# Esquem_tico.net
KiCad netlist of a schematic drawn in Altium Designer
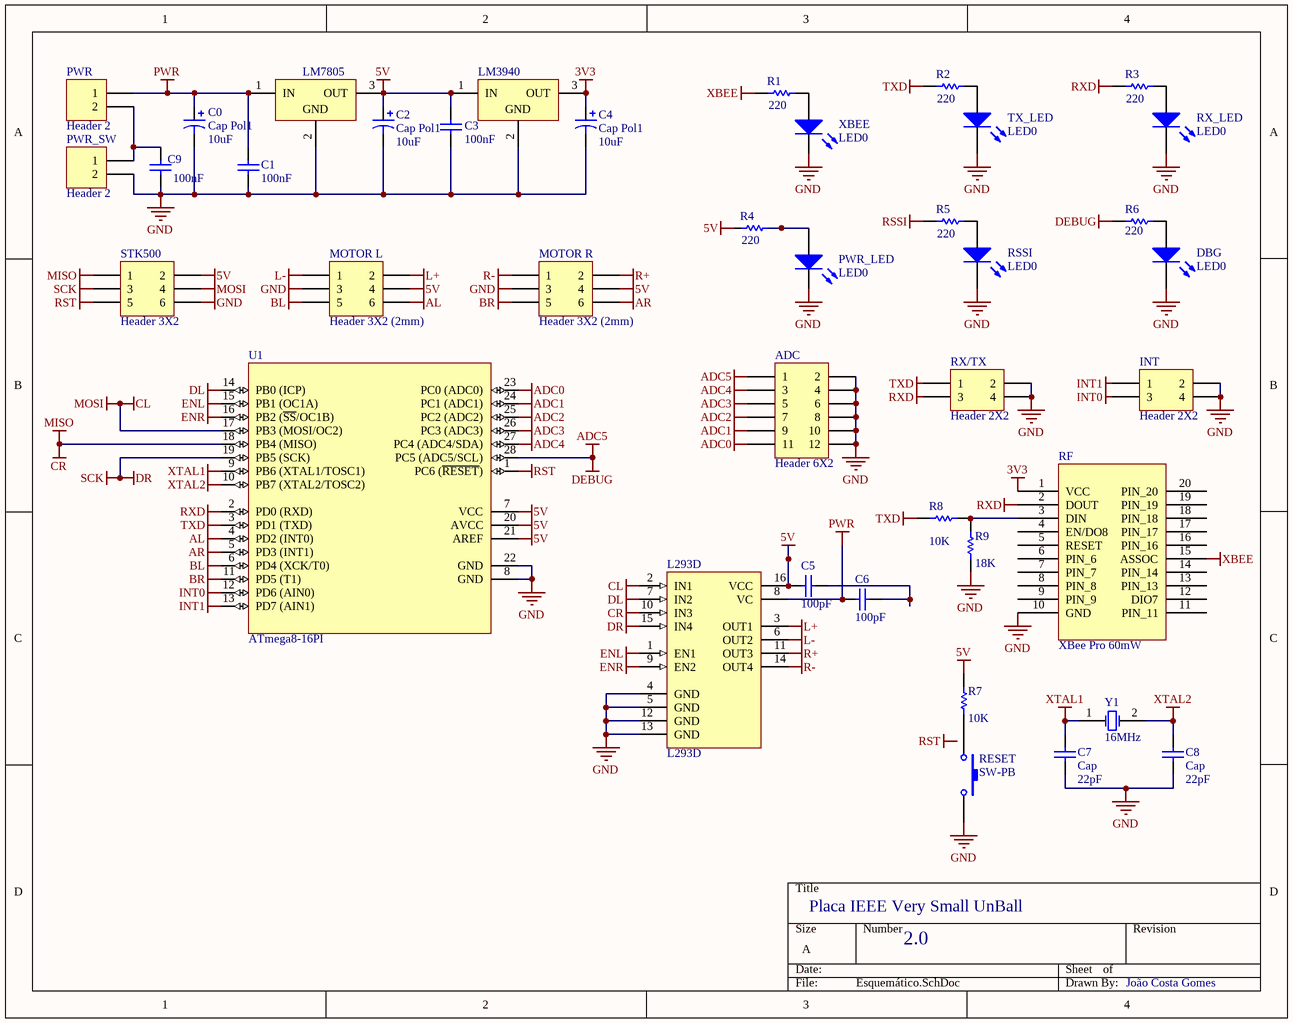
[diagram p0: Esquemático.SchDoc]

(export (version "E")
  (design (tool "Eeschema 10.0.6"))
  (components
    (comp (ref "ADC")
      (value "Header 6X2")
      (footprint "HDR2X6")
      (description "Header, 6-Pin, Dual row")
      (fields (field (name "PUBLISHER") "Altium Limited"))
      (libsource (lib "Miscellaneous Connectors") (part "Header 6X2"))
    )
    (comp (ref "C0")
      (value "Cap Pol1")
      (footprint "footprintsGPSrev1:B")
      (description "Polarized Capacitor (Radial)")
      (fields (field (name "ALTIUM_VALUE") "10uF") (field (name "PUBLISHER") "Altium Limited"))
      (libsource (lib "Miscellaneous Devices") (part "Cap Pol1"))
    )
    (comp (ref "C1")
      (value "100nF")
      (footprint "footprintsGPSrev1:C_NANO_HOLES")
      (description "Capacitor")
      (fields (field (name "Comment") "Cap") (field (name "PUBLISHER") "Altium Limited"))
      (libsource (lib "Miscellaneous Devices") (part "Cap"))
    )
    (comp (ref "C2")
      (value "Cap Pol1")
      (footprint "footprintsGPSrev1:B")
      (description "Polarized Capacitor (Radial)")
      (fields (field (name "ALTIUM_VALUE") "10uF") (field (name "PUBLISHER") "Altium Limited"))
      (libsource (lib "Miscellaneous Devices") (part "Cap Pol1"))
    )
    (comp (ref "C3")
      (value "100nF")
      (footprint "footprintsGPSrev1:C_NANO_HOLES")
      (description "Capacitor")
      (fields (field (name "Comment") "Cap") (field (name "PUBLISHER") "Altium Limited"))
      (libsource (lib "Miscellaneous Devices") (part "Cap"))
    )
    (comp (ref "C4")
      (value "Cap Pol1")
      (footprint "footprintsGPSrev1:B")
      (description "Polarized Capacitor (Radial)")
      (fields (field (name "ALTIUM_VALUE") "10uF") (field (name "PUBLISHER") "Altium Limited"))
      (libsource (lib "Miscellaneous Devices") (part "Cap Pol1"))
    )
    (comp (ref "C5")
      (value "100pF")
      (footprint "footprintsGPSrev1:C_NANO_HOLES")
      (description "Capacitor")
      (fields (field (name "Comment") "Cap") (field (name "PUBLISHER") "Altium Limited"))
      (libsource (lib "Miscellaneous Devices") (part "Cap"))
    )
    (comp (ref "C6")
      (value "100pF")
      (footprint "C_NANO_HOLES")
      (description "Capacitor")
      (fields (field (name "Comment") "Cap") (field (name "PUBLISHER") "Altium Limited"))
      (libsource (lib "Miscellaneous Devices") (part "Cap"))
    )
    (comp (ref "C7")
      (value "Cap")
      (footprint "C_NANO_HOLES")
      (description "Capacitor")
      (fields (field (name "ALTIUM_VALUE") "22pF") (field (name "PUBLISHER") "Altium Limited"))
      (libsource (lib "Miscellaneous Devices") (part "Cap"))
    )
    (comp (ref "C8")
      (value "Cap")
      (footprint "C_NANO_HOLES")
      (description "Capacitor")
      (fields (field (name "ALTIUM_VALUE") "22pF") (field (name "PUBLISHER") "Altium Limited"))
      (libsource (lib "Miscellaneous Devices") (part "Cap"))
    )
    (comp (ref "C9")
      (value "100nF")
      (footprint "footprintsGPSrev1:C_NANO_HOLES")
      (description "Capacitor")
      (fields (field (name "Comment") "Cap") (field (name "PUBLISHER") "Altium Limited"))
      (libsource (lib "Miscellaneous Devices") (part "Cap"))
    )
    (comp (ref "DBG")
      (value "LED0")
      (footprint "B")
      (description "Typical INFRARED GaAs LED")
      (fields (field (name "PUBLISHER") "Altium Limited"))
      (libsource (lib "Miscellaneous Devices") (part "LED0"))
    )
    (comp (ref "INT")
      (value "Header 2X2")
      (footprint "HDR2X2")
      (description "Header, 2-Pin, Dual row")
      (fields (field (name "PUBLISHER") "Altium Limited"))
      (libsource (lib "Miscellaneous Connectors") (part "Header 2X2"))
    )
    (comp (ref "L293D")
      (value "L293D")
      (footprint "DIP16")
      (description "Push-Pull Four Channel Driver With Diode")
      (fields (field (name "PUBLISHER") "Altium Limited"))
      (libsource (lib "ST Interface DC & Stepper Motor Controller") (part "L293D"))
    )
    (comp (ref "LM3940")
      (value "LM3940IT-3.3")
      (footprint "T03B")
      (description "1A Low Dropout Regulator for 5V to 3.3V Conversion")
      (fields
        (field (name "MANUFACTURER") "National Semiconductor")
        (field (name "DIGIKEYPARTNUMBER") "LM3940IT-3.3-ND")
        (field (name "PUBLISHER") "Altium Limited")
      )
      (libsource (lib "NSC LDO") (part "LM3940IT-3.3"))
    )
    (comp (ref "LM7805")
      (value "µA7805CKC")
      (footprint "KC03")
      (description "Positive-Voltage Regulator")
      (fields (field (name "PUBLISHER") "Altium Limited"))
      (libsource (lib "TI Power Mgt Voltage Regulator") (part "µA7805CKC"))
    )
    (comp (ref "MOTOR L")
      (value "Header 3X2 (2mm)")
      (footprint "HDR2X3")
      (description "Header, 3-Pin, Dual row")
      (fields (field (name "PUBLISHER") "Altium Limited"))
      (libsource (lib "Miscellaneous Connectors") (part "Header 3X2"))
    )
    (comp (ref "MOTOR R")
      (value "Header 3X2 (2mm)")
      (footprint "HDR2X3")
      (description "Header, 3-Pin, Dual row")
      (fields (field (name "PUBLISHER") "Altium Limited"))
      (libsource (lib "Miscellaneous Connectors") (part "Header 3X2"))
    )
    (comp (ref "PWR")
      (value "Header 2")
      (footprint "HDR1X2")
      (description "Header, 2-Pin")
      (fields (field (name "PUBLISHER") "Altium Limited"))
      (libsource (lib "Miscellaneous Connectors") (part "Header 2"))
    )
    (comp (ref "PWR_LED")
      (value "LED0")
      (footprint "B")
      (description "Typical INFRARED GaAs LED")
      (fields (field (name "PUBLISHER") "Altium Limited"))
      (libsource (lib "Miscellaneous Devices") (part "LED0"))
    )
    (comp (ref "PWR_SW")
      (value "Header 2")
      (footprint "HDR1X2")
      (description "Header, 2-Pin")
      (fields (field (name "PUBLISHER") "Altium Limited"))
      (libsource (lib "Miscellaneous Connectors") (part "Header 2"))
    )
    (comp (ref "R1")
      (value "220")
      (footprint "AXIAL-0.3")
      (description "Resistor")
      (fields (field (name "PUBLISHER") "Altium Limited"))
      (libsource (lib "Miscellaneous Devices") (part "Res1"))
    )
    (comp (ref "R2")
      (value "220")
      (footprint "AXIAL-0.3")
      (description "Resistor")
      (fields (field (name "PUBLISHER") "Altium Limited"))
      (libsource (lib "Miscellaneous Devices") (part "Res1"))
    )
    (comp (ref "R3")
      (value "220")
      (footprint "AXIAL-0.3")
      (description "Resistor")
      (fields (field (name "PUBLISHER") "Altium Limited"))
      (libsource (lib "Miscellaneous Devices") (part "Res1"))
    )
    (comp (ref "R4")
      (value "220")
      (footprint "AXIAL-0.3")
      (description "Resistor")
      (fields (field (name "PUBLISHER") "Altium Limited"))
      (libsource (lib "Miscellaneous Devices") (part "Res1"))
    )
    (comp (ref "R5")
      (value "220")
      (footprint "AXIAL-0.3")
      (description "Resistor")
      (fields (field (name "PUBLISHER") "Altium Limited"))
      (libsource (lib "Miscellaneous Devices") (part "Res1"))
    )
    (comp (ref "R6")
      (value "220")
      (footprint "AXIAL-0.3")
      (description "Resistor")
      (fields (field (name "PUBLISHER") "Altium Limited"))
      (libsource (lib "Miscellaneous Devices") (part "Res1"))
    )
    (comp (ref "R7")
      (value "10K")
      (footprint "AXIAL-0.3")
      (description "Resistor")
      (fields (field (name "PUBLISHER") "Altium Limited"))
      (libsource (lib "Miscellaneous Devices") (part "Res1"))
    )
    (comp (ref "R8")
      (value "10K")
      (footprint "AXIAL-0.3")
      (description "Resistor")
      (fields (field (name "PUBLISHER") "Altium Limited"))
      (libsource (lib "Miscellaneous Devices") (part "Res1"))
    )
    (comp (ref "R9")
      (value "18K")
      (footprint "AXIAL-0.3")
      (description "Resistor")
      (fields (field (name "PUBLISHER") "Altium Limited"))
      (libsource (lib "Miscellaneous Devices") (part "Res1"))
    )
    (comp (ref "RESET")
      (value "SW-PB")
      (footprint "PUSHBUTTON")
      (description "Switch")
      (fields (field (name "PUBLISHER") "Altium Limited"))
      (libsource (lib "Miscellaneous Devices") (part "SW-PB"))
    )
    (comp (ref "RF") (value "XBee Pro 60mW") (footprint "XBEE_PRO") (libsource (lib "Schlib") (part "XBee")))
    (comp (ref "RSSI")
      (value "LED0")
      (footprint "B")
      (description "Typical INFRARED GaAs LED")
      (fields (field (name "PUBLISHER") "Altium Limited"))
      (libsource (lib "Miscellaneous Devices") (part "LED0"))
    )
    (comp (ref "RX/TX")
      (value "Header 2X2")
      (footprint "HDR2X2")
      (description "Header, 2-Pin, Dual row")
      (fields (field (name "PUBLISHER") "Altium Limited"))
      (libsource (lib "Miscellaneous Connectors") (part "Header 2X2"))
    )
    (comp (ref "RX_LED")
      (value "LED0")
      (footprint "B")
      (description "Typical INFRARED GaAs LED")
      (fields (field (name "PUBLISHER") "Altium Limited"))
      (libsource (lib "Miscellaneous Devices") (part "LED0"))
    )
    (comp (ref "STK500")
      (value "Header 3X2")
      (footprint "HDR2X3")
      (description "Header, 3-Pin, Dual row")
      (fields (field (name "PUBLISHER") "Altium Limited"))
      (libsource (lib "Miscellaneous Connectors") (part "Header 3X2"))
    )
    (comp (ref "TX_LED")
      (value "LED0")
      (footprint "footprintsGPSrev1:B")
      (description "Typical INFRARED GaAs LED")
      (fields (field (name "PUBLISHER") "Altium Limited"))
      (libsource (lib "Miscellaneous Devices") (part "LED0"))
    )
    (comp (ref "U1")
      (value "ATmega8-16PI")
      (footprint "28P3")
      (description "8-Bit AVR Microcontroller with 8K Bytes of In-System Programmable Flash Memory")
      (fields (field (name "PUBLISHER") "Altium Limited"))
      (libsource (lib "Atmel Microcontroller 8-Bit AVR") (part "ATmega8-16PI"))
    )
    (comp (ref "XBEE")
      (value "LED0")
      (footprint "footprintsGPSrev1:B")
      (description "Typical INFRARED GaAs LED")
      (fields (field (name "PUBLISHER") "Altium Limited"))
      (libsource (lib "Miscellaneous Devices") (part "LED0"))
    )
    (comp (ref "Y1")
      (value "16MHz")
      (footprint "HC-49U")
      (description "Crystal Oscillator")
      (fields (field (name "PUBLISHER") "Altium Limited"))
      (libsource (lib "ECS Crystal Oscillator") (part "ECS-120-32-1"))
    )
  )
  (nets
    (net (code "1") (name "3V3") (class "Default")
      (node (ref "C4") (pin "1") (pinfunction "1_1") (pintype "passive"))
      (node (ref "LM3940") (pin "3") (pinfunction "OUT_3") (pintype "power_in"))
      (node (ref "RF") (pin "1") (pinfunction "VCC_1") (pintype "passive"))
    )
    (net (code "2") (name "5V") (class "Default")
      (node (ref "C2") (pin "1") (pinfunction "1_1") (pintype "passive"))
      (node (ref "C3") (pin "1") (pinfunction "1_1") (pintype "passive"))
      (node (ref "C5") (pin "1") (pinfunction "1_1") (pintype "passive"))
      (node (ref "L293D") (pin "16") (pinfunction "VCC_16") (pintype "power_in"))
      (node (ref "LM3940") (pin "1") (pinfunction "IN_1") (pintype "power_in"))
      (node (ref "LM7805") (pin "3") (pinfunction "OUT_3") (pintype "power_in"))
      (node (ref "MOTOR L") (pin "4") (pinfunction "4_4") (pintype "passive"))
      (node (ref "MOTOR R") (pin "4") (pinfunction "4_4") (pintype "passive"))
      (node (ref "R7") (pin "2") (pinfunction "2_2") (pintype "passive"))
      (node (ref "STK500") (pin "2") (pinfunction "2_2") (pintype "passive"))
      (node (ref "U1") (pin "20") (pinfunction "AVCC_20") (pintype "power_in"))
      (node (ref "U1") (pin "21") (pinfunction "AREF_21") (pintype "passive"))
      (node (ref "U1") (pin "7") (pinfunction "VCC_7") (pintype "power_in"))
    )
    (net (code "3") (name "ADC0") (class "Default")
      (node (ref "ADC") (pin "11") (pinfunction "11_11") (pintype "passive"))
      (node (ref "U1") (pin "23") (pinfunction "PC0_(ADC0)_23") (pintype "bidirectional"))
    )
    (net (code "4") (name "ADC1") (class "Default")
      (node (ref "ADC") (pin "9") (pinfunction "9_9") (pintype "passive"))
      (node (ref "U1") (pin "24") (pinfunction "PC1_(ADC1)_24") (pintype "bidirectional"))
    )
    (net (code "5") (name "ADC2") (class "Default")
      (node (ref "ADC") (pin "7") (pinfunction "7_7") (pintype "passive"))
      (node (ref "U1") (pin "25") (pinfunction "PC2_(ADC2)_25") (pintype "bidirectional"))
    )
    (net (code "6") (name "ADC3") (class "Default")
      (node (ref "ADC") (pin "5") (pinfunction "5_5") (pintype "passive"))
      (node (ref "U1") (pin "26") (pinfunction "PC3_(ADC3)_26") (pintype "bidirectional"))
    )
    (net (code "7") (name "ADC4") (class "Default")
      (node (ref "ADC") (pin "3") (pinfunction "3_3") (pintype "passive"))
      (node (ref "U1") (pin "27") (pinfunction "PC4_(ADC4/SDA)_27") (pintype "bidirectional"))
    )
    (net (code "8") (name "ADC5") (class "Default")
      (node (ref "ADC") (pin "1") (pinfunction "1_1") (pintype "passive"))
      (node (ref "R6") (pin "1") (pinfunction "1_1") (pintype "passive"))
      (node (ref "U1") (pin "28") (pinfunction "PC5_(ADC5/SCL)_28") (pintype "bidirectional"))
    )
    (net (code "9") (name "AL") (class "Default")
      (node (ref "MOTOR L") (pin "6") (pinfunction "6_6") (pintype "passive"))
      (node (ref "U1") (pin "4") (pinfunction "PD2_(INT0)_4") (pintype "bidirectional"))
    )
    (net (code "10") (name "AR") (class "Default")
      (node (ref "MOTOR R") (pin "6") (pinfunction "6_6") (pintype "passive"))
      (node (ref "U1") (pin "5") (pinfunction "PD3_(INT1)_5") (pintype "bidirectional"))
    )
    (net (code "11") (name "BL") (class "Default")
      (node (ref "MOTOR L") (pin "5") (pinfunction "5_5") (pintype "passive"))
      (node (ref "U1") (pin "6") (pinfunction "PD4_(XCK/T0)_6") (pintype "bidirectional"))
    )
    (net (code "12") (name "BR") (class "Default")
      (node (ref "MOTOR R") (pin "5") (pinfunction "5_5") (pintype "passive"))
      (node (ref "U1") (pin "11") (pinfunction "PD5_(T1)_11") (pintype "bidirectional"))
    )
    (net (code "13") (name "CL") (class "Default")
      (node (ref "L293D") (pin "2") (pinfunction "IN1_2") (pintype "input"))
      (node (ref "STK500") (pin "4") (pinfunction "4_4") (pintype "passive"))
      (node (ref "U1") (pin "17") (pinfunction "PB3_(MOSI/OC2)_17") (pintype "bidirectional"))
    )
    (net (code "14") (name "CR") (class "Default")
      (node (ref "L293D") (pin "10") (pinfunction "IN3_10") (pintype "input"))
      (node (ref "STK500") (pin "1") (pinfunction "1_1") (pintype "passive"))
      (node (ref "U1") (pin "18") (pinfunction "PB4_(MISO)_18") (pintype "bidirectional"))
    )
    (net (code "15") (name "DL") (class "Default")
      (node (ref "L293D") (pin "7") (pinfunction "IN2_7") (pintype "input"))
      (node (ref "U1") (pin "14") (pinfunction "PB0_(ICP)_14") (pintype "bidirectional"))
    )
    (net (code "16") (name "DR") (class "Default")
      (node (ref "L293D") (pin "15") (pinfunction "IN4_15") (pintype "input"))
      (node (ref "STK500") (pin "3") (pinfunction "3_3") (pintype "passive"))
      (node (ref "U1") (pin "19") (pinfunction "PB5_(SCK)_19") (pintype "bidirectional"))
    )
    (net (code "17") (name "ENL") (class "Default")
      (node (ref "L293D") (pin "1") (pinfunction "EN1_1") (pintype "input"))
      (node (ref "U1") (pin "15") (pinfunction "PB1_(OC1A)_15") (pintype "bidirectional"))
    )
    (net (code "18") (name "ENR") (class "Default")
      (node (ref "L293D") (pin "9") (pinfunction "EN2_9") (pintype "input"))
      (node (ref "U1") (pin "16") (pinfunction "PB2_(~{SS}/OC1B)_16") (pintype "bidirectional"))
    )
    (net (code "19") (name "GND") (class "Default")
      (node (ref "ADC") (pin "10") (pinfunction "10_10") (pintype "passive"))
      (node (ref "ADC") (pin "12") (pinfunction "12_12") (pintype "passive"))
      (node (ref "ADC") (pin "2") (pinfunction "2_2") (pintype "passive"))
      (node (ref "ADC") (pin "4") (pinfunction "4_4") (pintype "passive"))
      (node (ref "ADC") (pin "6") (pinfunction "6_6") (pintype "passive"))
      (node (ref "ADC") (pin "8") (pinfunction "8_8") (pintype "passive"))
      (node (ref "C0") (pin "2") (pinfunction "2_2") (pintype "passive"))
      (node (ref "C1") (pin "2") (pinfunction "2_2") (pintype "passive"))
      (node (ref "C2") (pin "2") (pinfunction "2_2") (pintype "passive"))
      (node (ref "C3") (pin "2") (pinfunction "2_2") (pintype "passive"))
      (node (ref "C4") (pin "2") (pinfunction "2_2") (pintype "passive"))
      (node (ref "C7") (pin "2") (pinfunction "2_2") (pintype "passive"))
      (node (ref "C8") (pin "2") (pinfunction "2_2") (pintype "passive"))
      (node (ref "C9") (pin "2") (pinfunction "2_2") (pintype "passive"))
      (node (ref "DBG") (pin "2") (pinfunction "K_2") (pintype "passive"))
      (node (ref "INT") (pin "2") (pinfunction "2_2") (pintype "passive"))
      (node (ref "INT") (pin "4") (pinfunction "4_4") (pintype "passive"))
      (node (ref "L293D") (pin "12") (pinfunction "GND_12") (pintype "power_in"))
      (node (ref "L293D") (pin "13") (pinfunction "GND_13") (pintype "power_in"))
      (node (ref "L293D") (pin "4") (pinfunction "GND_4") (pintype "power_in"))
      (node (ref "L293D") (pin "5") (pinfunction "GND_5") (pintype "power_in"))
      (node (ref "LM3940") (pin "2") (pinfunction "GND_2") (pintype "power_in"))
      (node (ref "LM7805") (pin "2") (pinfunction "GND_2") (pintype "power_in"))
      (node (ref "MOTOR L") (pin "3") (pinfunction "3_3") (pintype "passive"))
      (node (ref "MOTOR R") (pin "3") (pinfunction "3_3") (pintype "passive"))
      (node (ref "PWR_SW") (pin "2") (pinfunction "2_2") (pintype "passive"))
      (node (ref "R9") (pin "2") (pinfunction "2_2") (pintype "passive"))
      (node (ref "RESET") (pin "2") (pinfunction "2_2") (pintype "passive"))
      (node (ref "RF") (pin "10") (pinfunction "GND_10") (pintype "passive"))
      (node (ref "RSSI") (pin "2") (pinfunction "K_2") (pintype "passive"))
      (node (ref "RX/TX") (pin "2") (pinfunction "2_2") (pintype "passive"))
      (node (ref "RX/TX") (pin "4") (pinfunction "4_4") (pintype "passive"))
      (node (ref "RX_LED") (pin "2") (pinfunction "K_2") (pintype "passive"))
      (node (ref "STK500") (pin "6") (pinfunction "6_6") (pintype "passive"))
      (node (ref "TX_LED") (pin "2") (pinfunction "K_2") (pintype "passive"))
      (node (ref "U1") (pin "22") (pinfunction "GND_22") (pintype "power_in"))
      (node (ref "U1") (pin "8") (pinfunction "GND_8") (pintype "power_in"))
    )
    (net (code "20") (name "INT0") (class "Default")
      (node (ref "U1") (pin "12") (pinfunction "PD6_(AIN0)_12") (pintype "bidirectional"))
    )
    (net (code "21") (name "INT1") (class "Default")
      (node (ref "U1") (pin "13") (pinfunction "PD7_(AIN1)_13") (pintype "bidirectional"))
    )
    (net (code "22") (name "L+") (class "Default")
      (node (ref "L293D") (pin "3") (pinfunction "OUT1_3") (pintype "tri_state"))
      (node (ref "MOTOR L") (pin "2") (pinfunction "2_2") (pintype "passive"))
    )
    (net (code "23") (name "L-") (class "Default")
      (node (ref "L293D") (pin "6") (pinfunction "OUT2_6") (pintype "tri_state"))
      (node (ref "MOTOR L") (pin "1") (pinfunction "1_1") (pintype "passive"))
    )
    (net (code "24") (name "Net-(C5-Pad2)") (class "Default")
      (node (ref "C5") (pin "2") (pinfunction "2_2") (pintype "passive"))
      (node (ref "C6") (pin "2") (pinfunction "2_2") (pintype "passive"))
    )
    (net (code "25") (name "Net-(C9-Pad1)") (class "Default")
      (node (ref "C9") (pin "1") (pinfunction "1_1") (pintype "passive"))
      (node (ref "PWR") (pin "2") (pinfunction "2_2") (pintype "passive"))
      (node (ref "PWR_SW") (pin "1") (pinfunction "1_1") (pintype "passive"))
    )
    (net (code "26") (name "Net-(DBG-A)") (class "Default")
      (node (ref "DBG") (pin "1") (pinfunction "A_1") (pintype "passive"))
      (node (ref "R6") (pin "2") (pinfunction "2_2") (pintype "passive"))
    )
    (net (code "27") (name "Net-(PWR_LED-A)") (class "Default")
      (node (ref "PWR_LED") (pin "1") (pinfunction "A_1") (pintype "passive"))
      (node (ref "R4") (pin "2") (pinfunction "2_2") (pintype "passive"))
    )
    (net (code "28") (name "Net-(R7-Pad1)") (class "Default")
      (node (ref "R7") (pin "1") (pinfunction "1_1") (pintype "passive"))
      (node (ref "RESET") (pin "1") (pinfunction "1_1") (pintype "passive"))
    )
    (net (code "29") (name "Net-(RF-DIN)") (class "Default")
      (node (ref "R8") (pin "1") (pinfunction "1_1") (pintype "passive"))
      (node (ref "R9") (pin "1") (pinfunction "1_1") (pintype "passive"))
      (node (ref "RF") (pin "3") (pinfunction "DIN_3") (pintype "passive"))
    )
    (net (code "30") (name "Net-(RSSI-A)") (class "Default")
      (node (ref "R5") (pin "2") (pinfunction "2_2") (pintype "passive"))
      (node (ref "RSSI") (pin "1") (pinfunction "A_1") (pintype "passive"))
    )
    (net (code "31") (name "Net-(RX_LED-A)") (class "Default")
      (node (ref "R3") (pin "2") (pinfunction "2_2") (pintype "passive"))
      (node (ref "RX_LED") (pin "1") (pinfunction "A_1") (pintype "passive"))
    )
    (net (code "32") (name "Net-(TX_LED-A)") (class "Default")
      (node (ref "R2") (pin "2") (pinfunction "2_2") (pintype "passive"))
      (node (ref "TX_LED") (pin "1") (pinfunction "A_1") (pintype "passive"))
    )
    (net (code "33") (name "Net-(XBEE-A)") (class "Default")
      (node (ref "R1") (pin "2") (pinfunction "2_2") (pintype "passive"))
      (node (ref "XBEE") (pin "1") (pinfunction "A_1") (pintype "passive"))
    )
    (net (code "34") (name "PWR") (class "Default")
      (node (ref "C0") (pin "1") (pinfunction "1_1") (pintype "passive"))
      (node (ref "C1") (pin "1") (pinfunction "1_1") (pintype "passive"))
      (node (ref "C6") (pin "1") (pinfunction "1_1") (pintype "passive"))
      (node (ref "L293D") (pin "8") (pinfunction "VC_8") (pintype "power_in"))
      (node (ref "LM7805") (pin "1") (pinfunction "IN_1") (pintype "power_in"))
      (node (ref "PWR") (pin "1") (pinfunction "1_1") (pintype "passive"))
    )
    (net (code "35") (name "R+") (class "Default")
      (node (ref "L293D") (pin "11") (pinfunction "OUT3_11") (pintype "tri_state"))
      (node (ref "MOTOR R") (pin "2") (pinfunction "2_2") (pintype "passive"))
    )
    (net (code "36") (name "R-") (class "Default")
      (node (ref "L293D") (pin "14") (pinfunction "OUT4_14") (pintype "tri_state"))
      (node (ref "MOTOR R") (pin "1") (pinfunction "1_1") (pintype "passive"))
    )
    (net (code "37") (name "RSSI") (class "Default")
      (node (ref "R5") (pin "1") (pinfunction "1_1") (pintype "passive"))
    )
    (net (code "38") (name "RST") (class "Default")
      (node (ref "STK500") (pin "5") (pinfunction "5_5") (pintype "passive"))
      (node (ref "U1") (pin "1") (pinfunction "PC6_(~{RESET})_1") (pintype "bidirectional"))
    )
    (net (code "39") (name "RXD") (class "Default")
      (node (ref "R3") (pin "1") (pinfunction "1_1") (pintype "passive"))
      (node (ref "RF") (pin "2") (pinfunction "DOUT_2") (pintype "passive"))
      (node (ref "U1") (pin "2") (pinfunction "PD0_(RXD)_2") (pintype "bidirectional"))
    )
    (net (code "40") (name "TXD") (class "Default")
      (node (ref "R2") (pin "1") (pinfunction "1_1") (pintype "passive"))
      (node (ref "R8") (pin "2") (pinfunction "2_2") (pintype "passive"))
      (node (ref "U1") (pin "3") (pinfunction "PD1_(TXD)_3") (pintype "bidirectional"))
    )
    (net (code "41") (name "XBEE") (class "Default")
      (node (ref "R1") (pin "1") (pinfunction "1_1") (pintype "passive"))
      (node (ref "RF") (pin "15") (pinfunction "ASSOC_15") (pintype "passive"))
    )
    (net (code "42") (name "XTAL1") (class "Default")
      (node (ref "C7") (pin "1") (pinfunction "1_1") (pintype "passive"))
      (node (ref "U1") (pin "9") (pinfunction "PB6_(XTAL1/TOSC1)_9") (pintype "bidirectional"))
      (node (ref "Y1") (pin "1") (pinfunction "OSC1_1") (pintype "passive"))
    )
    (net (code "43") (name "XTAL2") (class "Default")
      (node (ref "C8") (pin "1") (pinfunction "1_1") (pintype "passive"))
      (node (ref "U1") (pin "10") (pinfunction "PB7_(XTAL2/TOSC2)_10") (pintype "bidirectional"))
      (node (ref "Y1") (pin "2") (pinfunction "OSC2_2") (pintype "passive"))
    )
    (net (code "44") (name "unconnected-(INT-Pad1)") (class "Default")
      (node (ref "INT") (pin "1") (pinfunction "1_1") (pintype "passive"))
    )
    (net (code "45") (name "unconnected-(INT-Pad3)") (class "Default")
      (node (ref "INT") (pin "3") (pinfunction "3_3") (pintype "passive"))
    )
    (net (code "46") (name "unconnected-(PWR_LED-K-Pad2)") (class "Default")
      (node (ref "PWR_LED") (pin "2") (pinfunction "K_2") (pintype "passive"))
    )
    (net (code "47") (name "unconnected-(R4-Pad1)") (class "Default")
      (node (ref "R4") (pin "1") (pinfunction "1_1") (pintype "passive"))
    )
    (net (code "48") (name "unconnected-(RF-DIO7-Pad12)") (class "Default")
      (node (ref "RF") (pin "12") (pinfunction "DIO7_12") (pintype "passive"))
    )
    (net (code "49") (name "unconnected-(RF-EN{slash}DO8-Pad4)") (class "Default")
      (node (ref "RF") (pin "4") (pinfunction "EN/DO8_4") (pintype "passive"))
    )
    (net (code "50") (name "unconnected-(RF-PIN_6-Pad6)") (class "Default")
      (node (ref "RF") (pin "6") (pinfunction "PIN_6_6") (pintype "passive"))
    )
    (net (code "51") (name "unconnected-(RF-PIN_7-Pad7)") (class "Default")
      (node (ref "RF") (pin "7") (pinfunction "PIN_7_7") (pintype "passive"))
    )
    (net (code "52") (name "unconnected-(RF-PIN_8-Pad8)") (class "Default")
      (node (ref "RF") (pin "8") (pinfunction "PIN_8_8") (pintype "passive"))
    )
    (net (code "53") (name "unconnected-(RF-PIN_9-Pad9)") (class "Default")
      (node (ref "RF") (pin "9") (pinfunction "PIN_9_9") (pintype "passive"))
    )
    (net (code "54") (name "unconnected-(RF-PIN_11-Pad11)") (class "Default")
      (node (ref "RF") (pin "11") (pinfunction "PIN_11_11") (pintype "passive"))
    )
    (net (code "55") (name "unconnected-(RF-PIN_13-Pad13)") (class "Default")
      (node (ref "RF") (pin "13") (pinfunction "PIN_13_13") (pintype "passive"))
    )
    (net (code "56") (name "unconnected-(RF-PIN_14-Pad14)") (class "Default")
      (node (ref "RF") (pin "14") (pinfunction "PIN_14_14") (pintype "passive"))
    )
    (net (code "57") (name "unconnected-(RF-PIN_16-Pad16)") (class "Default")
      (node (ref "RF") (pin "16") (pinfunction "PIN_16_16") (pintype "passive"))
    )
    (net (code "58") (name "unconnected-(RF-PIN_17-Pad17)") (class "Default")
      (node (ref "RF") (pin "17") (pinfunction "PIN_17_17") (pintype "passive"))
    )
    (net (code "59") (name "unconnected-(RF-PIN_18-Pad18)") (class "Default")
      (node (ref "RF") (pin "18") (pinfunction "PIN_18_18") (pintype "passive"))
    )
    (net (code "60") (name "unconnected-(RF-PIN_19-Pad19)") (class "Default")
      (node (ref "RF") (pin "19") (pinfunction "PIN_19_19") (pintype "passive"))
    )
    (net (code "61") (name "unconnected-(RF-PIN_20-Pad20)") (class "Default")
      (node (ref "RF") (pin "20") (pinfunction "PIN_20_20") (pintype "passive"))
    )
    (net (code "62") (name "unconnected-(RF-RESET-Pad5)") (class "Default")
      (node (ref "RF") (pin "5") (pinfunction "RESET_5") (pintype "passive"))
    )
    (net (code "63") (name "unconnected-(RX/TX-Pad1)") (class "Default")
      (node (ref "RX/TX") (pin "1") (pinfunction "1_1") (pintype "passive"))
    )
    (net (code "64") (name "unconnected-(RX/TX-Pad3)") (class "Default")
      (node (ref "RX/TX") (pin "3") (pinfunction "3_3") (pintype "passive"))
    )
    (net (code "65") (name "unconnected-(XBEE-K-Pad2)") (class "Default")
      (node (ref "XBEE") (pin "2") (pinfunction "K_2") (pintype "passive"))
    )
  )
)
